# Sheet_V1_0_0.net
KiCad netlist of a schematic drawn in Altium Designer
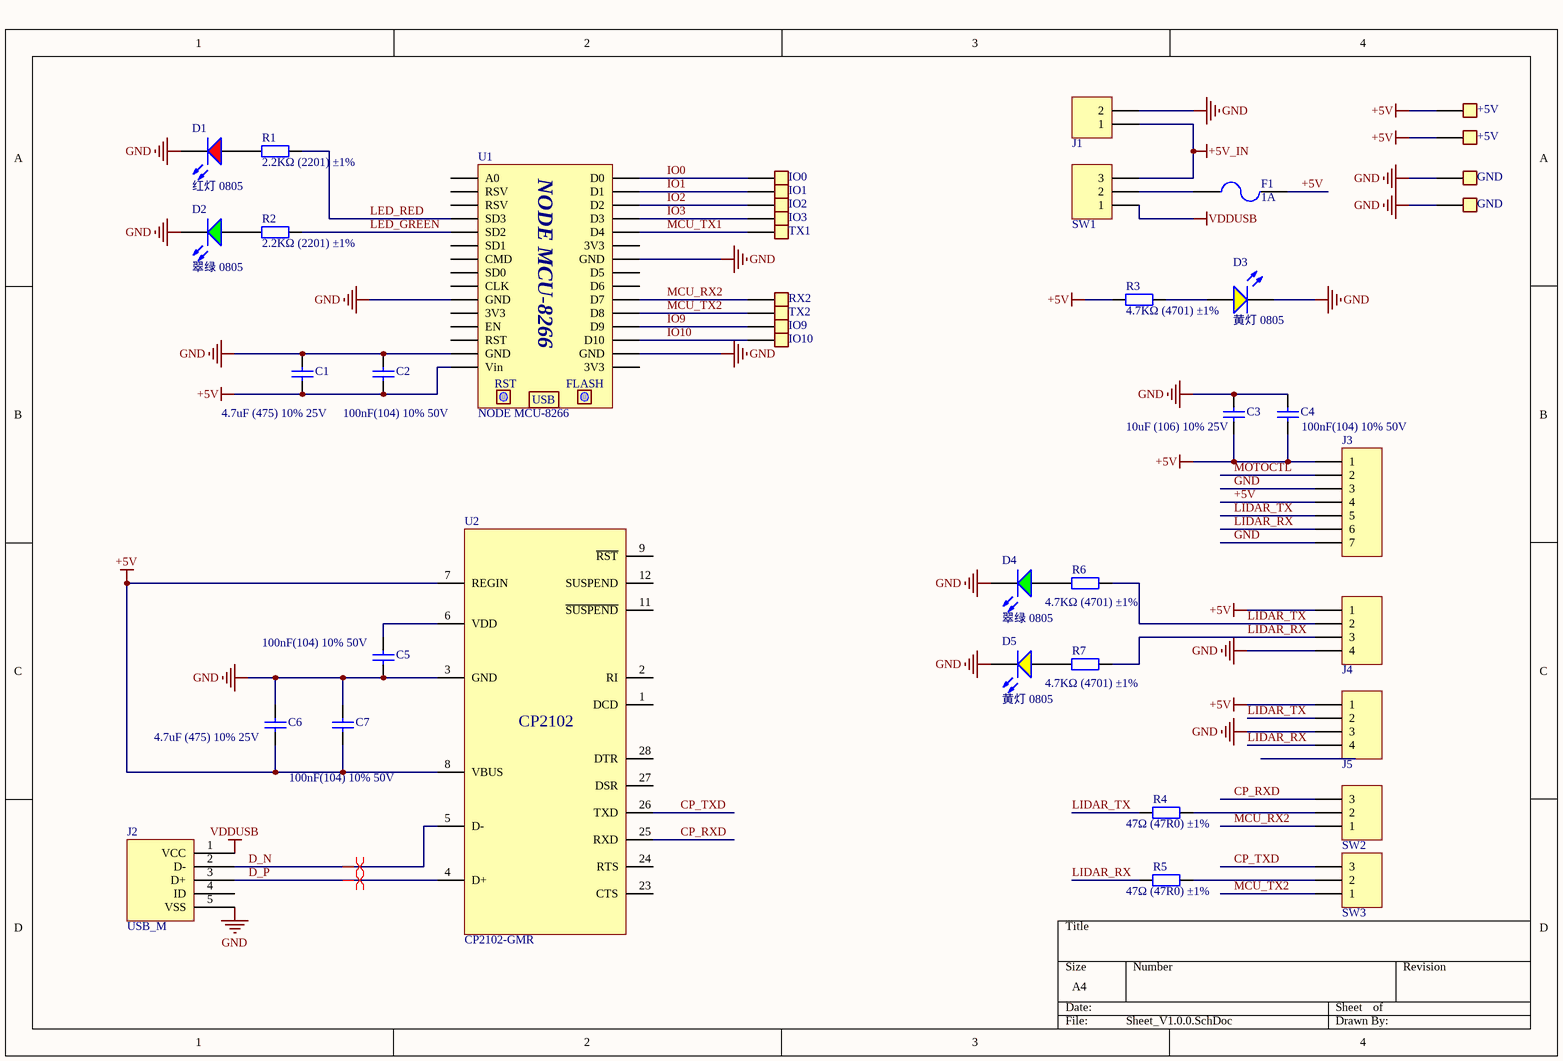
[diagram p0: Sheet_V1.0.0.SchDoc]

(export (version "E")
  (design (tool "Eeschema 10.0.6"))
  (components
    (comp (ref "C1")
      (value "4.7uF (475) 10% 25V")
      (footprint "0805_C")
      (description "贴片电容")
      (libsource (lib "Cap") (part "0805 4.7uF (475) 10% 25V"))
    )
    (comp (ref "C2")
      (value "100nF(104) 10% 50V")
      (footprint "0805_C")
      (description "贴片电容")
      (libsource (lib "Cap") (part "0805 100nF(104) 10% 50V"))
    )
    (comp (ref "C3")
      (value "10uF (106) 10% 25V")
      (footprint "0805_C")
      (description "贴片电容")
      (libsource (lib "Cap") (part "0805 10uF (106) 10% 25V"))
    )
    (comp (ref "C4")
      (value "100nF(104) 10% 50V")
      (footprint "0805_C")
      (description "贴片电容")
      (libsource (lib "Cap") (part "0805 100nF(104) 10% 50V"))
    )
    (comp (ref "C5")
      (value "100nF(104) 10% 50V")
      (footprint "0805_C")
      (description "贴片电容")
      (libsource (lib "Cap") (part "0805 100nF(104) 10% 50V"))
    )
    (comp (ref "C6")
      (value "4.7uF (475) 10% 25V")
      (footprint "0805_C")
      (description "贴片电容")
      (libsource (lib "Cap") (part "0805 4.7uF (475) 10% 25V"))
    )
    (comp (ref "C7")
      (value "100nF(104) 10% 50V")
      (footprint "0805_C")
      (description "贴片电容")
      (libsource (lib "Cap") (part "0805 100nF(104) 10% 50V"))
    )
    (comp (ref "D1")
      (value "红灯 0805")
      (footprint "0805_LED_S1")
      (description "发光二极管")
      (libsource (lib "LED") (part "0805 红灯"))
    )
    (comp (ref "D2")
      (value "翠绿 0805")
      (footprint "0805_LED_S1")
      (description "发光二极管")
      (libsource (lib "Miscellaneous Devices LC") (part "0805 翠绿"))
    )
    (comp (ref "D3")
      (value "黄灯 0805")
      (footprint "0805_LED_S1")
      (description "发光二极管")
      (libsource (lib "LED") (part "0805 黄灯"))
    )
    (comp (ref "D4")
      (value "翠绿 0805")
      (footprint "0805_LED_S1")
      (description "发光二极管")
      (libsource (lib "Miscellaneous Devices LC") (part "0805 翠绿"))
    )
    (comp (ref "D5")
      (value "黄灯 0805")
      (footprint "0805_LED_S1")
      (description "发光二极管")
      (libsource (lib "LED") (part "0805 黄灯"))
    )
    (comp (ref "F1")
      (value "1A")
      (footprint "1812")
      (description "保险丝")
      (fields (field (name "Comment") "Fuse") (field (name "PUBLISHER") "Altium Limited"))
      (libsource (lib "ghzhang") (part "Fuse 2"))
    )
    (comp (ref "J1")
      (value "Header 2")
      (footprint "MKDS3_2RMM")
      (description "接插件")
      (fields (field (name "PUBLISHER") "Altium Limited"))
      (libsource (lib "Miscellaneous Connectors") (part "Header 2"))
    )
    (comp (ref "J2")
      (value "USB_M")
      (footprint "USB-MICRO-A")
      (description "MicroUSB接口")
      (libsource (lib "ghzhang") (part "USB_M"))
    )
    (comp (ref "J3")
      (value "Header 7")
      (footprint "5267-7A")
      (description "Header, 7-Pin")
      (fields (field (name "PUBLISHER") "Altium Limited"))
      (libsource (lib "Miscellaneous Connectors") (part "Header 7"))
    )
    (comp (ref "J4")
      (value "Header 4")
      (footprint "PH2.0-4P")
      (description "接插件")
      (fields (field (name "PUBLISHER") "Altium Limited"))
      (libsource (lib "Miscellaneous Connectors") (part "Header 4"))
    )
    (comp (ref "J5")
      (value "Header 4")
      (description "接插件")
      (fields (field (name "PUBLISHER") "Altium Limited"))
      (libsource (lib "Miscellaneous Connectors") (part "Header 4"))
    )
    (comp (ref "R1")
      (value "2.2KΩ (2201) ±1%")
      (footprint "0805_R")
      (description "贴片电阻")
      (libsource (lib "Miscellaneous Devices LC") (part "0805 2.2KΩ (2201) 1%"))
    )
    (comp (ref "R2")
      (value "2.2KΩ (2201) ±1%")
      (footprint "0805_R")
      (description "贴片电阻")
      (libsource (lib "Miscellaneous Devices LC") (part "0805 2.2KΩ (2201) 1%"))
    )
    (comp (ref "R3")
      (value "4.7KΩ (4701) ±1%")
      (footprint "0805_R")
      (description "贴片电阻")
      (libsource (lib "") (part "0805 4.7KΩ (4701) 1%_1"))
    )
    (comp (ref "R4")
      (value "47Ω (47R0) ±1%")
      (footprint "0805_R")
      (description "贴片电阻")
      (libsource (lib "RES") (part "0805 47Ω (47R0) 1%"))
    )
    (comp (ref "R5")
      (value "47Ω (47R0) ±1%")
      (footprint "0805_R")
      (description "贴片电阻")
      (libsource (lib "RES") (part "0805 47Ω (47R0) 1%"))
    )
    (comp (ref "R6")
      (value "4.7KΩ (4701) ±1%")
      (footprint "0805_R")
      (description "贴片电阻")
      (libsource (lib "RES") (part "0805 4.7KΩ (4701) 1%"))
    )
    (comp (ref "R7")
      (value "4.7KΩ (4701) ±1%")
      (footprint "0805_R")
      (description "贴片电阻")
      (libsource (lib "RES") (part "0805 4.7KΩ (4701) 1%"))
    )
    (comp (ref "SW1")
      (value "Header 3")
      (footprint "HDR3X1_A")
      (description "接插件")
      (fields (field (name "PUBLISHER") "Altium Limited"))
      (libsource (lib "") (part "Header 3_1"))
    )
    (comp (ref "SW2")
      (value "Header 3")
      (footprint "HDR3X1_A")
      (description "接插件")
      (fields (field (name "PUBLISHER") "Altium Limited"))
      (libsource (lib "Miscellaneous Connectors") (part "Header 3"))
    )
    (comp (ref "SW3")
      (value "Header 3")
      (footprint "HDR3X1_A")
      (description "接插件")
      (fields (field (name "PUBLISHER") "Altium Limited"))
      (libsource (lib "Miscellaneous Connectors") (part "Header 3"))
    )
    (comp (ref "TP0") (value "IO0") (footprint "CHECK-A") (libsource (lib "原理图库") (part "TP")))
    (comp (ref "TP1") (value "IO1") (footprint "CHECK-A") (libsource (lib "原理图库") (part "TP")))
    (comp (ref "TP2") (value "IO2") (footprint "CHECK-A") (libsource (lib "原理图库") (part "TP")))
    (comp (ref "TP3") (value "IO3") (footprint "CHECK-A") (libsource (lib "原理图库") (part "TP")))
    (comp (ref "TP9") (value "IO9") (footprint "CHECK-A") (libsource (lib "原理图库") (part "TP")))
    (comp (ref "TP10") (value "IO10") (footprint "CHECK-A") (libsource (lib "原理图库") (part "TP")))
    (comp (ref "TP11") (value "TX1") (footprint "CHECK-A") (libsource (lib "原理图库") (part "TP")))
    (comp (ref "TP12") (value "RX2") (footprint "CHECK-A") (libsource (lib "原理图库") (part "TP")))
    (comp (ref "TP13") (value "TX2") (footprint "CHECK-A") (libsource (lib "原理图库") (part "TP")))
    (comp (ref "TP14") (value "+5V") (footprint "CHECK-A") (libsource (lib "原理图库") (part "TP")))
    (comp (ref "TP15") (value "+5V") (footprint "CHECK-A") (libsource (lib "原理图库") (part "TP")))
    (comp (ref "TP16") (value "GND") (footprint "CHECK-A") (libsource (lib "原理图库") (part "TP")))
    (comp (ref "TP17") (value "GND") (footprint "CHECK-A") (libsource (lib "原理图库") (part "TP")))
    (comp (ref "U1")
      (value "NODE MCU-8266")
      (footprint "ESP8266_CP2102")
      (libsource (lib "ghzhang") (part "NodeMCU_8266"))
    )
    (comp (ref "U2")
      (value "CP2102-GMR")
      (footprint "QFN-28_5x5x05P")
      (description "USB")
      (libsource (lib "IC") (part "CP2102-GMR_[C6568]"))
    )
  )
  (nets
    (net (code "1") (name "+5V") (class "Default")
      (node (ref "C1") (pin "1") (pinfunction "1_1") (pintype "passive"))
      (node (ref "C2") (pin "1") (pinfunction "1_1") (pintype "passive"))
      (node (ref "C3") (pin "1") (pinfunction "1_1") (pintype "passive"))
      (node (ref "C4") (pin "1") (pinfunction "1_1") (pintype "passive"))
      (node (ref "C6") (pin "1") (pinfunction "1_1") (pintype "passive"))
      (node (ref "C7") (pin "1") (pinfunction "1_1") (pintype "passive"))
      (node (ref "F1") (pin "2") (pinfunction "2_2") (pintype "passive"))
      (node (ref "J3") (pin "1") (pinfunction "1_1") (pintype "passive"))
      (node (ref "J3") (pin "4") (pinfunction "4_4") (pintype "passive"))
      (node (ref "J4") (pin "1") (pinfunction "1_1") (pintype "passive"))
      (node (ref "J5") (pin "1") (pinfunction "1_1") (pintype "passive"))
      (node (ref "R3") (pin "1") (pinfunction "1_1") (pintype "passive"))
      (node (ref "TP14") (pin "1") (pintype "passive"))
      (node (ref "TP15") (pin "1") (pintype "passive"))
      (node (ref "U1") (pin "15") (pinfunction "Vin_15") (pintype "passive"))
      (node (ref "U2") (pin "7") (pinfunction "REGIN_7") (pintype "passive"))
      (node (ref "U2") (pin "8") (pinfunction "VBUS_8") (pintype "passive"))
    )
    (net (code "2") (name "+5V_IN") (class "Default")
      (node (ref "J1") (pin "1") (pinfunction "1_1") (pintype "passive"))
      (node (ref "SW1") (pin "3") (pinfunction "3_3") (pintype "passive"))
    )
    (net (code "3") (name "/CP_RXD") (class "Default")
      (node (ref "SW2") (pin "3") (pinfunction "3_3") (pintype "passive"))
      (node (ref "U2") (pin "25") (pinfunction "RXD_25") (pintype "passive"))
    )
    (net (code "4") (name "/CP_TXD") (class "Default")
      (node (ref "SW3") (pin "3") (pinfunction "3_3") (pintype "passive"))
      (node (ref "U2") (pin "26") (pinfunction "TXD_26") (pintype "passive"))
    )
    (net (code "5") (name "/D_N") (class "Default")
      (node (ref "J2") (pin "2") (pinfunction "D-_2") (pintype "passive"))
      (node (ref "U2") (pin "5") (pinfunction "D-_5") (pintype "passive"))
    )
    (net (code "6") (name "/D_P") (class "Default")
      (node (ref "J2") (pin "3") (pinfunction "D+_3") (pintype "passive"))
      (node (ref "U2") (pin "4") (pinfunction "D+_4") (pintype "passive"))
    )
    (net (code "7") (name "/IO0") (class "Default")
      (node (ref "TP0") (pin "1") (pintype "passive"))
      (node (ref "U1") (pin "30") (pinfunction "D0_30") (pintype "passive"))
    )
    (net (code "8") (name "/IO1") (class "Default")
      (node (ref "TP1") (pin "1") (pintype "passive"))
      (node (ref "U1") (pin "29") (pinfunction "D1_29") (pintype "passive"))
    )
    (net (code "9") (name "/IO2") (class "Default")
      (node (ref "TP2") (pin "1") (pintype "passive"))
      (node (ref "U1") (pin "28") (pinfunction "D2_28") (pintype "passive"))
    )
    (net (code "10") (name "/IO3") (class "Default")
      (node (ref "TP3") (pin "1") (pintype "passive"))
      (node (ref "U1") (pin "27") (pinfunction "D3_27") (pintype "passive"))
    )
    (net (code "11") (name "/IO9") (class "Default")
      (node (ref "TP9") (pin "1") (pintype "passive"))
      (node (ref "U1") (pin "19") (pinfunction "D9_19") (pintype "passive"))
    )
    (net (code "12") (name "/IO10") (class "Default")
      (node (ref "TP10") (pin "1") (pintype "passive"))
      (node (ref "U1") (pin "18") (pinfunction "D10_18") (pintype "passive"))
    )
    (net (code "13") (name "/LED_GREEN") (class "Default")
      (node (ref "R2") (pin "1") (pinfunction "1_1") (pintype "passive"))
      (node (ref "U1") (pin "5") (pinfunction "SD2_5") (pintype "passive"))
    )
    (net (code "14") (name "/LED_RED") (class "Default")
      (node (ref "R1") (pin "1") (pinfunction "1_1") (pintype "passive"))
      (node (ref "U1") (pin "4") (pinfunction "SD3_4") (pintype "passive"))
    )
    (net (code "15") (name "/LIDAR_RX") (class "Default")
      (node (ref "J3") (pin "6") (pinfunction "6_6") (pintype "passive"))
      (node (ref "J4") (pin "3") (pinfunction "3_3") (pintype "passive"))
      (node (ref "J5") (pin "4") (pinfunction "4_4") (pintype "passive"))
      (node (ref "R5") (pin "1") (pinfunction "1_1") (pintype "passive"))
      (node (ref "R7") (pin "1") (pinfunction "1_1") (pintype "passive"))
    )
    (net (code "16") (name "/LIDAR_TX") (class "Default")
      (node (ref "J3") (pin "5") (pinfunction "5_5") (pintype "passive"))
      (node (ref "J4") (pin "2") (pinfunction "2_2") (pintype "passive"))
      (node (ref "J5") (pin "2") (pinfunction "2_2") (pintype "passive"))
      (node (ref "R4") (pin "1") (pinfunction "1_1") (pintype "passive"))
      (node (ref "R6") (pin "1") (pinfunction "1_1") (pintype "passive"))
    )
    (net (code "17") (name "/MCU_RX2") (class "Default")
      (node (ref "SW2") (pin "1") (pinfunction "1_1") (pintype "passive"))
      (node (ref "TP12") (pin "1") (pintype "passive"))
      (node (ref "U1") (pin "21") (pinfunction "D7_21") (pintype "passive"))
    )
    (net (code "18") (name "/MCU_TX1") (class "Default")
      (node (ref "TP11") (pin "1") (pintype "passive"))
      (node (ref "U1") (pin "26") (pinfunction "D4_26") (pintype "passive"))
    )
    (net (code "19") (name "/MCU_TX2") (class "Default")
      (node (ref "SW3") (pin "1") (pinfunction "1_1") (pintype "passive"))
      (node (ref "TP13") (pin "1") (pintype "passive"))
      (node (ref "U1") (pin "20") (pinfunction "D8_20") (pintype "passive"))
    )
    (net (code "20") (name "/MOTOCTL") (class "Default")
      (node (ref "J3") (pin "2") (pinfunction "2_2") (pintype "passive"))
    )
    (net (code "21") (name "GND") (class "Default")
      (node (ref "C1") (pin "2") (pinfunction "2_2") (pintype "passive"))
      (node (ref "C2") (pin "2") (pinfunction "2_2") (pintype "passive"))
      (node (ref "C3") (pin "2") (pinfunction "2_2") (pintype "passive"))
      (node (ref "C4") (pin "2") (pinfunction "2_2") (pintype "passive"))
      (node (ref "C5") (pin "1") (pinfunction "1_1") (pintype "passive"))
      (node (ref "C6") (pin "2") (pinfunction "2_2") (pintype "passive"))
      (node (ref "C7") (pin "2") (pinfunction "2_2") (pintype "passive"))
      (node (ref "D1") (pin "K") (pinfunction "K_K") (pintype "passive"))
      (node (ref "D2") (pin "K") (pinfunction "K_K") (pintype "passive"))
      (node (ref "D3") (pin "K") (pinfunction "K_K") (pintype "passive"))
      (node (ref "D4") (pin "K") (pinfunction "K_K") (pintype "passive"))
      (node (ref "D5") (pin "K") (pinfunction "K_K") (pintype "passive"))
      (node (ref "J1") (pin "2") (pinfunction "2_2") (pintype "passive"))
      (node (ref "J2") (pin "5") (pinfunction "VSS_5") (pintype "passive"))
      (node (ref "J3") (pin "3") (pinfunction "3_3") (pintype "passive"))
      (node (ref "J3") (pin "7") (pinfunction "7_7") (pintype "passive"))
      (node (ref "J4") (pin "4") (pinfunction "4_4") (pintype "passive"))
      (node (ref "J5") (pin "3") (pinfunction "3_3") (pintype "passive"))
      (node (ref "TP16") (pin "1") (pintype "passive"))
      (node (ref "TP17") (pin "1") (pintype "passive"))
      (node (ref "U1") (pin "10") (pinfunction "GND_10") (pintype "passive"))
      (node (ref "U1") (pin "14") (pinfunction "GND_14") (pintype "passive"))
      (node (ref "U1") (pin "17") (pinfunction "GND_17") (pintype "passive"))
      (node (ref "U1") (pin "24") (pinfunction "GND_24") (pintype "passive"))
      (node (ref "U2") (pin "3") (pinfunction "GND_3") (pintype "passive"))
    )
    (net (code "22") (name "Net-(D1-PadA)") (class "Default")
      (node (ref "D1") (pin "A") (pinfunction "A_A") (pintype "passive"))
      (node (ref "R1") (pin "2") (pinfunction "2_2") (pintype "passive"))
    )
    (net (code "23") (name "Net-(D2-PadA)") (class "Default")
      (node (ref "D2") (pin "A") (pinfunction "A_A") (pintype "passive"))
      (node (ref "R2") (pin "2") (pinfunction "2_2") (pintype "passive"))
    )
    (net (code "24") (name "Net-(D3-PadA)") (class "Default")
      (node (ref "D3") (pin "A") (pinfunction "A_A") (pintype "passive"))
      (node (ref "R3") (pin "2") (pinfunction "2_2") (pintype "passive"))
    )
    (net (code "25") (name "Net-(D4-PadA)") (class "Default")
      (node (ref "D4") (pin "A") (pinfunction "A_A") (pintype "passive"))
      (node (ref "R6") (pin "2") (pinfunction "2_2") (pintype "passive"))
    )
    (net (code "26") (name "Net-(D5-PadA)") (class "Default")
      (node (ref "D5") (pin "A") (pinfunction "A_A") (pintype "passive"))
      (node (ref "R7") (pin "2") (pinfunction "2_2") (pintype "passive"))
    )
    (net (code "27") (name "Net-(F1-Pad1)") (class "Default")
      (node (ref "F1") (pin "1") (pinfunction "1_1") (pintype "passive"))
      (node (ref "SW1") (pin "2") (pinfunction "2_2") (pintype "passive"))
    )
    (net (code "28") (name "Net-(R4-Pad2)") (class "Default")
      (node (ref "R4") (pin "2") (pinfunction "2_2") (pintype "passive"))
      (node (ref "SW2") (pin "2") (pinfunction "2_2") (pintype "passive"))
    )
    (net (code "29") (name "Net-(R5-Pad2)") (class "Default")
      (node (ref "R5") (pin "2") (pinfunction "2_2") (pintype "passive"))
      (node (ref "SW3") (pin "2") (pinfunction "2_2") (pintype "passive"))
    )
    (net (code "30") (name "Net-(U2-VDD)") (class "Default")
      (node (ref "C5") (pin "2") (pinfunction "2_2") (pintype "passive"))
      (node (ref "U2") (pin "6") (pinfunction "VDD_6") (pintype "passive"))
    )
    (net (code "31") (name "VDDUSB") (class "Default")
      (node (ref "J2") (pin "1") (pinfunction "VCC_1") (pintype "passive"))
      (node (ref "SW1") (pin "1") (pinfunction "1_1") (pintype "passive"))
    )
    (net (code "32") (name "unconnected-(J2-ID-Pad4)") (class "Default")
      (node (ref "J2") (pin "4") (pinfunction "ID_4") (pintype "passive"))
    )
    (net (code "33") (name "unconnected-(U1-3V3-Pad11)") (class "Default")
      (node (ref "U1") (pin "11") (pinfunction "3V3_11") (pintype "passive"))
    )
    (net (code "34") (name "unconnected-(U1-3V3-Pad16)") (class "Default")
      (node (ref "U1") (pin "16") (pinfunction "3V3_16") (pintype "passive"))
    )
    (net (code "35") (name "unconnected-(U1-3V3-Pad25)") (class "Default")
      (node (ref "U1") (pin "25") (pinfunction "3V3_25") (pintype "passive"))
    )
    (net (code "36") (name "unconnected-(U1-A0-Pad1)") (class "Default")
      (node (ref "U1") (pin "1") (pinfunction "A0_1") (pintype "passive"))
    )
    (net (code "37") (name "unconnected-(U1-CLK-Pad9)") (class "Default")
      (node (ref "U1") (pin "9") (pinfunction "CLK_9") (pintype "passive"))
    )
    (net (code "38") (name "unconnected-(U1-CMD-Pad7)") (class "Default")
      (node (ref "U1") (pin "7") (pinfunction "CMD_7") (pintype "passive"))
    )
    (net (code "39") (name "unconnected-(U1-D5-Pad23)") (class "Default")
      (node (ref "U1") (pin "23") (pinfunction "D5_23") (pintype "passive"))
    )
    (net (code "40") (name "unconnected-(U1-D6-Pad22)") (class "Default")
      (node (ref "U1") (pin "22") (pinfunction "D6_22") (pintype "passive"))
    )
    (net (code "41") (name "unconnected-(U1-EN-Pad12)") (class "Default")
      (node (ref "U1") (pin "12") (pinfunction "EN_12") (pintype "passive"))
    )
    (net (code "42") (name "unconnected-(U1-RST-Pad13)") (class "Default")
      (node (ref "U1") (pin "13") (pinfunction "RST_13") (pintype "passive"))
    )
    (net (code "43") (name "unconnected-(U1-RSV-Pad2)") (class "Default")
      (node (ref "U1") (pin "2") (pinfunction "RSV_2") (pintype "passive"))
    )
    (net (code "44") (name "unconnected-(U1-RSV-Pad3)") (class "Default")
      (node (ref "U1") (pin "3") (pinfunction "RSV_3") (pintype "passive"))
    )
    (net (code "45") (name "unconnected-(U1-SD0-Pad8)") (class "Default")
      (node (ref "U1") (pin "8") (pinfunction "SD0_8") (pintype "passive"))
    )
    (net (code "46") (name "unconnected-(U1-SD1-Pad6)") (class "Default")
      (node (ref "U1") (pin "6") (pinfunction "SD1_6") (pintype "passive"))
    )
    (net (code "47") (name "unconnected-(U2-CTS-Pad23)") (class "Default")
      (node (ref "U2") (pin "23") (pinfunction "CTS_23") (pintype "passive"))
    )
    (net (code "48") (name "unconnected-(U2-DCD-Pad1)") (class "Default")
      (node (ref "U2") (pin "1") (pinfunction "DCD_1") (pintype "passive"))
    )
    (net (code "49") (name "unconnected-(U2-DSR-Pad27)") (class "Default")
      (node (ref "U2") (pin "27") (pinfunction "DSR_27") (pintype "passive"))
    )
    (net (code "50") (name "unconnected-(U2-DTR-Pad28)") (class "Default")
      (node (ref "U2") (pin "28") (pinfunction "DTR_28") (pintype "passive"))
    )
    (net (code "51") (name "unconnected-(U2-RI-Pad2)") (class "Default")
      (node (ref "U2") (pin "2") (pinfunction "RI_2") (pintype "passive"))
    )
    (net (code "52") (name "unconnected-(U2-RTS-Pad24)") (class "Default")
      (node (ref "U2") (pin "24") (pinfunction "RTS_24") (pintype "passive"))
    )
    (net (code "53") (name "unconnected-(U2-SUSPEND-Pad12)") (class "Default")
      (node (ref "U2") (pin "12") (pinfunction "SUSPEND_12") (pintype "passive"))
    )
    (net (code "54") (name "unconnected-(U2-~{RST}-Pad9)") (class "Default")
      (node (ref "U2") (pin "9") (pinfunction "~{RST}_9") (pintype "passive"))
    )
    (net (code "55") (name "unconnected-(U2-~{SUSPEND}-Pad11)") (class "Default")
      (node (ref "U2") (pin "11") (pinfunction "~{SUSPEND}_11") (pintype "passive"))
    )
  )
)
